# 14-CONNECTOR.net
KiCad netlist of a schematic drawn in Altium Designer
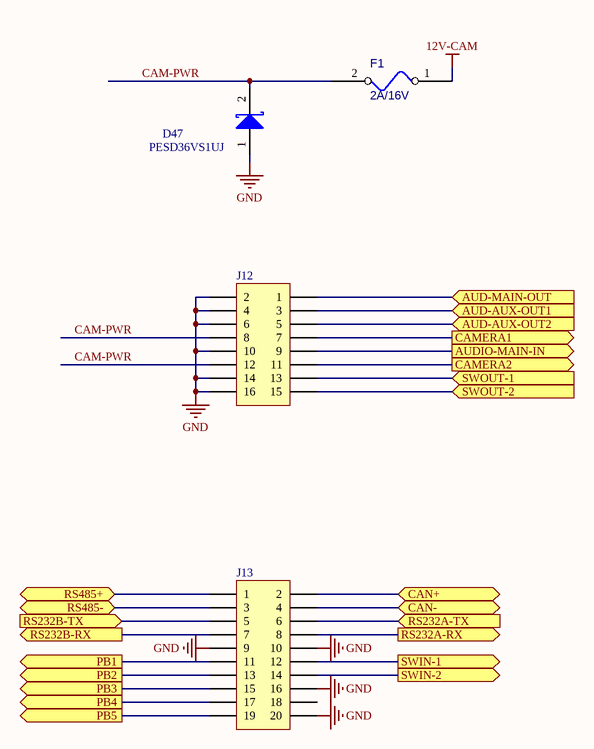
[diagram p0: 14-CONNECTOR.SchDoc]

(export (version "E")
  (design (tool "Eeschema 10.0.6"))
  (components
    (comp (ref "D47")
      (value "PESD36VS1UJ")
      (footprint "SOD323")
      (description "Schottky Rectifier")
      (libsource (lib "Miscellaneous Devices") (part "Diode 11DQ03"))
    )
    (comp (ref "F1") (value "2A/16V") (footprint "2920") (libsource (lib "*") (part "2A_32VDC_0467-002")))
    (comp (ref "J12")
      (value "Header 8X2")
      (footprint "3030WR-S-2*8P")
      (description "Header, 8-Pin, Dual row")
      (fields (field (name "PUBLISHER") "Altium Limited"))
      (libsource (lib "Miscellaneous Connectors") (part "Header 8X2"))
    )
    (comp (ref "J13")
      (value "Header 10X2")
      (footprint "3030WR-S-2*10P")
      (description "Header, 10-Pin, Dual row")
      (fields (field (name "PUBLISHER") "Altium Limited"))
      (libsource (lib "Miscellaneous Connectors") (part "Header 10X2"))
    )
  )
  (nets
    (net (code "1") (name "/AUD-AUX-OUT1") (class "Default")
      (node (ref "J12") (pin "3") (pinfunction "3_3") (pintype "passive"))
    )
    (net (code "2") (name "/AUD-AUX-OUT2") (class "Default")
      (node (ref "J12") (pin "5") (pinfunction "5_5") (pintype "passive"))
    )
    (net (code "3") (name "/AUD-MAIN-OUT") (class "Default")
      (node (ref "J12") (pin "1") (pinfunction "1_1") (pintype "passive"))
    )
    (net (code "4") (name "/AUDIO-MAIN-IN") (class "Default")
      (node (ref "J12") (pin "9") (pinfunction "9_9") (pintype "passive"))
    )
    (net (code "5") (name "/CAM-PWR") (class "Default")
      (node (ref "D47") (pin "2") (pinfunction "K_2") (pintype "passive"))
      (node (ref "F1") (pin "2") (pinfunction "2_2") (pintype "passive"))
      (node (ref "J12") (pin "12") (pinfunction "12_12") (pintype "passive"))
      (node (ref "J12") (pin "8") (pinfunction "8_8") (pintype "passive"))
    )
    (net (code "6") (name "/CAMERA1") (class "Default")
      (node (ref "J12") (pin "7") (pinfunction "7_7") (pintype "passive"))
    )
    (net (code "7") (name "/CAMERA2") (class "Default")
      (node (ref "J12") (pin "11") (pinfunction "11_11") (pintype "passive"))
    )
    (net (code "8") (name "/CAN+") (class "Default")
      (node (ref "J13") (pin "2") (pinfunction "2_2") (pintype "passive"))
    )
    (net (code "9") (name "/CAN-") (class "Default")
      (node (ref "J13") (pin "4") (pinfunction "4_4") (pintype "passive"))
    )
    (net (code "10") (name "/PB1") (class "Default")
      (node (ref "J13") (pin "11") (pinfunction "11_11") (pintype "passive"))
    )
    (net (code "11") (name "/PB2") (class "Default")
      (node (ref "J13") (pin "13") (pinfunction "13_13") (pintype "passive"))
    )
    (net (code "12") (name "/PB3") (class "Default")
      (node (ref "J13") (pin "15") (pinfunction "15_15") (pintype "passive"))
    )
    (net (code "13") (name "/PB4") (class "Default")
      (node (ref "J13") (pin "17") (pinfunction "17_17") (pintype "passive"))
    )
    (net (code "14") (name "/PB5") (class "Default")
      (node (ref "J13") (pin "19") (pinfunction "19_19") (pintype "passive"))
    )
    (net (code "15") (name "/RS232A-RX") (class "Default")
      (node (ref "J13") (pin "8") (pinfunction "8_8") (pintype "passive"))
    )
    (net (code "16") (name "/RS232A-TX") (class "Default")
      (node (ref "J13") (pin "6") (pinfunction "6_6") (pintype "passive"))
    )
    (net (code "17") (name "/RS232B-RX") (class "Default")
      (node (ref "J13") (pin "7") (pinfunction "7_7") (pintype "passive"))
    )
    (net (code "18") (name "/RS232B-TX") (class "Default")
      (node (ref "J13") (pin "5") (pinfunction "5_5") (pintype "passive"))
    )
    (net (code "19") (name "/RS485+") (class "Default")
      (node (ref "J13") (pin "1") (pinfunction "1_1") (pintype "passive"))
    )
    (net (code "20") (name "/RS485-") (class "Default")
      (node (ref "J13") (pin "3") (pinfunction "3_3") (pintype "passive"))
    )
    (net (code "21") (name "/SWIN-1") (class "Default")
      (node (ref "J13") (pin "12") (pinfunction "12_12") (pintype "passive"))
    )
    (net (code "22") (name "/SWIN-2") (class "Default")
      (node (ref "J13") (pin "14") (pinfunction "14_14") (pintype "passive"))
    )
    (net (code "23") (name "/SWOUT-1") (class "Default")
      (node (ref "J12") (pin "13") (pinfunction "13_13") (pintype "passive"))
    )
    (net (code "24") (name "/SWOUT-2") (class "Default")
      (node (ref "J12") (pin "15") (pinfunction "15_15") (pintype "passive"))
    )
    (net (code "25") (name "12V-CAM") (class "Default")
      (node (ref "F1") (pin "1") (pinfunction "1_1") (pintype "passive"))
    )
    (net (code "26") (name "GND") (class "Default")
      (node (ref "D47") (pin "1") (pinfunction "A_1") (pintype "passive"))
      (node (ref "J12") (pin "10") (pinfunction "10_10") (pintype "passive"))
      (node (ref "J12") (pin "14") (pinfunction "14_14") (pintype "passive"))
      (node (ref "J12") (pin "16") (pinfunction "16_16") (pintype "passive"))
      (node (ref "J12") (pin "2") (pinfunction "2_2") (pintype "passive"))
      (node (ref "J12") (pin "4") (pinfunction "4_4") (pintype "passive"))
      (node (ref "J12") (pin "6") (pinfunction "6_6") (pintype "passive"))
      (node (ref "J13") (pin "10") (pinfunction "10_10") (pintype "passive"))
      (node (ref "J13") (pin "16") (pinfunction "16_16") (pintype "passive"))
      (node (ref "J13") (pin "20") (pinfunction "20_20") (pintype "passive"))
      (node (ref "J13") (pin "9") (pinfunction "9_9") (pintype "passive"))
    )
    (net (code "27") (name "unconnected-(J13-Pad18)") (class "Default")
      (node (ref "J13") (pin "18") (pinfunction "18_18") (pintype "passive"))
    )
  )
)
